# control.net
KiCad netlist of a schematic drawn in EAGLE
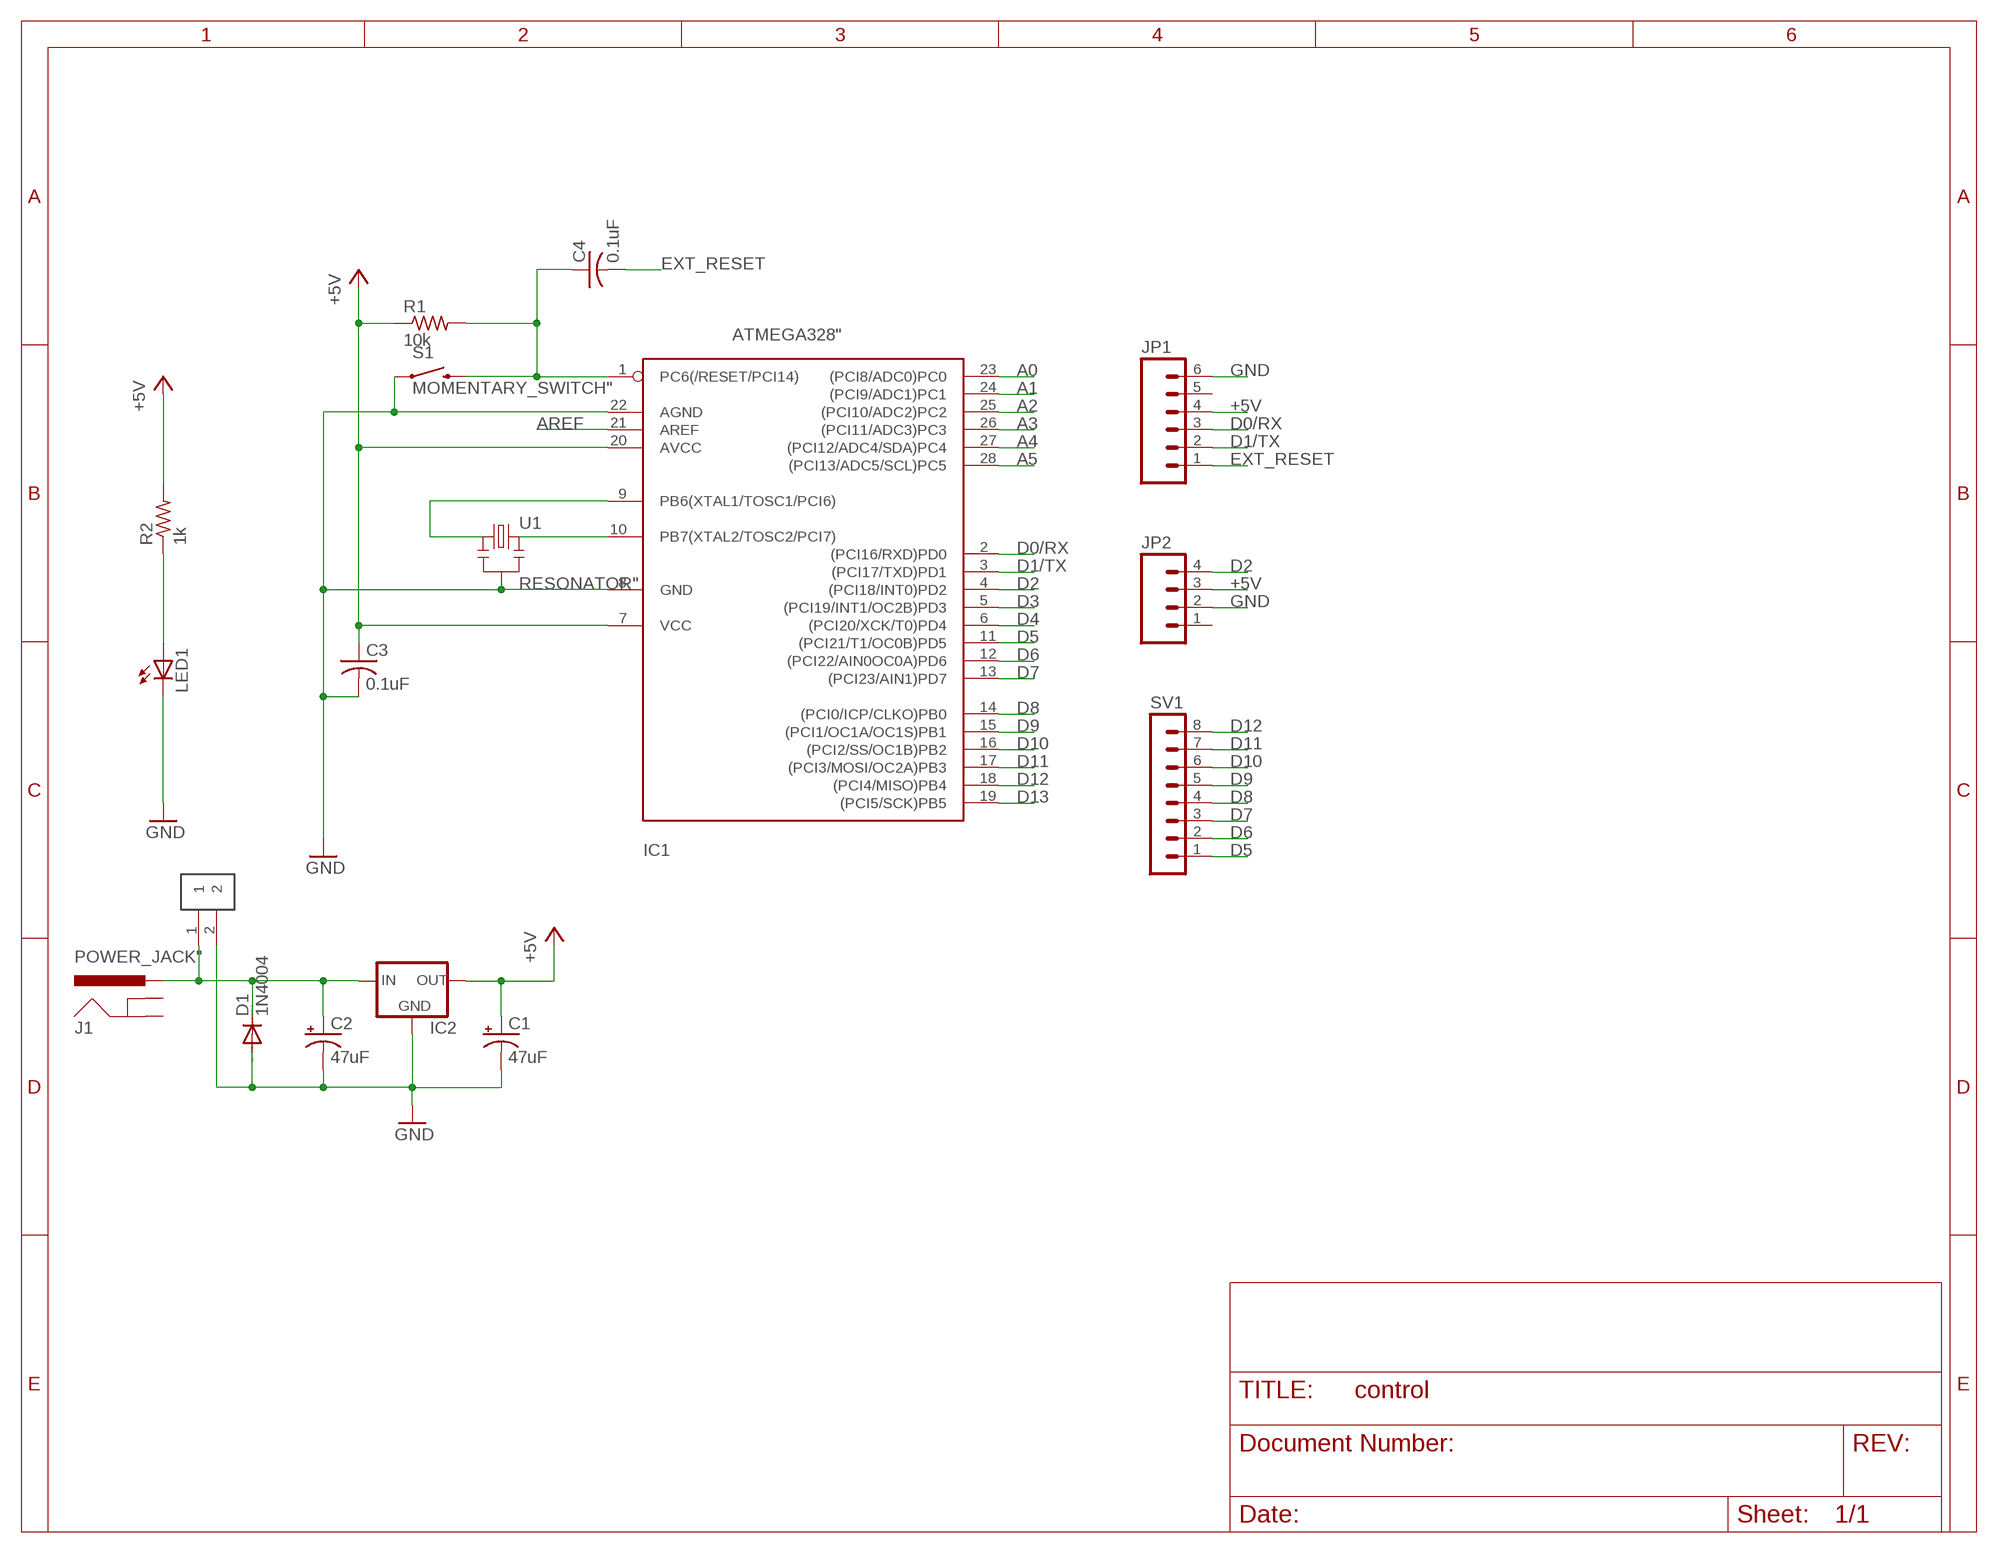
[diagram p0: schematic, sheet 1]

(export (version "E")
  (design (tool "Eeschema 10.0.6"))
  (components
    (comp (ref "C1")
      (value "47uF")
      (footprint "eagle-import:ELECTROLYTIC_CAP")
      (libsource (lib "eagle-import") (part "ELECTROLYTIC_CAP2.54MM"))
    )
    (comp (ref "C2")
      (value "47uF")
      (footprint "eagle-import:ELECTROLYTIC_CAP")
      (libsource (lib "eagle-import") (part "ELECTROLYTIC_CAP2.54MM"))
    )
    (comp (ref "C3")
      (value "0.1uF")
      (footprint "eagle-import:UNPOLARIZED_CAP")
      (libsource (lib "eagle-import") (part "UNPOLARIZED_CAP{dblquote}"))
    )
    (comp (ref "C4")
      (value "0.1uF")
      (footprint "eagle-import:UNPOLARIZED_CAP")
      (libsource (lib "eagle-import") (part "UNPOLARIZED_CAP{dblquote}"))
    )
    (comp (ref "D1")
      (value "1N4004")
      (footprint "eagle-import:DO41-10")
      (libsource (lib "eagle-import") (part "1N4004"))
    )
    (comp (ref "IC1")
      (value "ATMEGA328\"")
      (footprint "eagle-import:ATMEGA328")
      (libsource (lib "eagle-import") (part "ATMEGA328{dblquote}"))
    )
    (comp (ref "IC2")
      (value "REGULATOR")
      (footprint "eagle-import:L4931_REGULATOR")
      (libsource (lib "eagle-import") (part "REGULATOR"))
    )
    (comp (ref "J1")
      (value "POWER_JACK\"")
      (footprint "eagle-import:POWER_JACK")
      (libsource (lib "eagle-import") (part "POWER_JACK{dblquote}"))
    )
    (comp (ref "JP1")
      (value "1X06_HEADER\"")
      (footprint "eagle-import:1X06_HEADER")
      (libsource (lib "eagle-import") (part "1X06_HEADER{dblquote}"))
    )
    (comp (ref "JP2")
      (value "1X04_HEADER\"")
      (footprint "eagle-import:1X04_HEADER")
      (libsource (lib "eagle-import") (part "1X04_HEADER{dblquote}"))
    )
    (comp (ref "LED1")
      (value "LED3MM")
      (footprint "eagle-import:LED")
      (libsource (lib "eagle-import") (part "LED3MM"))
    )
    (comp (ref "R1")
      (value "10k")
      (footprint "eagle-import:RESISTOR")
      (libsource (lib "eagle-import") (part "RESISTOR1/6WATT"))
    )
    (comp (ref "R2")
      (value "1k")
      (footprint "eagle-import:RESISTOR")
      (libsource (lib "eagle-import") (part "RESISTOR1/6WATT"))
    )
    (comp (ref "S1")
      (value "MOMENTARY_SWITCH\"")
      (footprint "eagle-import:MOMENTARY_SWITCH")
      (libsource (lib "eagle-import") (part "MOMENTARY_SWITCH{dblquote}"))
    )
    (comp (ref "SV1")
      (value "MA08-1")
      (footprint "eagle-import:MA08-1")
      (libsource (lib "eagle-import") (part "MA08-1"))
    )
    (comp (ref "U$1")
      (value "1X02_HEADER")
      (footprint "eagle-import:1X02_HEADER")
      (libsource (lib "eagle-import") (part "1X02_HEADER"))
    )
    (comp (ref "U1")
      (value "RESONATOR\"")
      (footprint "eagle-import:RESONATOR")
      (libsource (lib "eagle-import") (part "RESONATOR{dblquote}"))
    )
  )
  (nets
    (net (code "1") (name "+5V") (class "Default")
      (node (ref "C1") (pin "+") (pinfunction "+_+") (pintype "passive"))
      (node (ref "C3") (pin "1") (pinfunction "1_1") (pintype "passive"))
      (node (ref "IC1") (pin "20") (pinfunction "AVCC_20") (pintype "bidirectional"))
      (node (ref "IC1") (pin "7") (pinfunction "VCC_7") (pintype "bidirectional"))
      (node (ref "IC2") (pin "OUT") (pinfunction "OUT_OUT") (pintype "passive"))
      (node (ref "JP1") (pin "4") (pinfunction "4_4") (pintype "passive"))
      (node (ref "JP2") (pin "3") (pinfunction "3_3") (pintype "passive"))
      (node (ref "R1") (pin "1") (pinfunction "1_1") (pintype "passive"))
      (node (ref "R2") (pin "2") (pinfunction "2_2") (pintype "passive"))
    )
    (net (code "2") (name "/A0") (class "Default")
      (node (ref "IC1") (pin "23") (pinfunction "(PCI8/ADC0)PC0_23") (pintype "bidirectional"))
    )
    (net (code "3") (name "/A1") (class "Default")
      (node (ref "IC1") (pin "24") (pinfunction "(PCI9/ADC1)PC1_24") (pintype "bidirectional"))
    )
    (net (code "4") (name "/A2") (class "Default")
      (node (ref "IC1") (pin "25") (pinfunction "(PCI10/ADC2)PC2_25") (pintype "bidirectional"))
    )
    (net (code "5") (name "/A3") (class "Default")
      (node (ref "IC1") (pin "26") (pinfunction "(PCI11/ADC3)PC3_26") (pintype "bidirectional"))
    )
    (net (code "6") (name "/A4") (class "Default")
      (node (ref "IC1") (pin "27") (pinfunction "(PCI12/ADC4/SDA)PC4_27") (pintype "bidirectional"))
    )
    (net (code "7") (name "/A5") (class "Default")
      (node (ref "IC1") (pin "28") (pinfunction "(PCI13/ADC5/SCL)PC5_28") (pintype "bidirectional"))
    )
    (net (code "8") (name "/AREF") (class "Default")
      (node (ref "IC1") (pin "21") (pinfunction "AREF_21") (pintype "bidirectional"))
    )
    (net (code "9") (name "/D0{slash}RX") (class "Default")
      (node (ref "IC1") (pin "2") (pinfunction "(PCI16/RXD)PD0_2") (pintype "bidirectional"))
      (node (ref "JP1") (pin "3") (pinfunction "3_3") (pintype "passive"))
    )
    (net (code "10") (name "/D1{slash}TX") (class "Default")
      (node (ref "IC1") (pin "3") (pinfunction "(PCI17/TXD)PD1_3") (pintype "bidirectional"))
      (node (ref "JP1") (pin "2") (pinfunction "2_2") (pintype "passive"))
    )
    (net (code "11") (name "/D2") (class "Default")
      (node (ref "IC1") (pin "4") (pinfunction "(PCI18/INT0)PD2_4") (pintype "bidirectional"))
      (node (ref "JP2") (pin "4") (pinfunction "4_4") (pintype "passive"))
    )
    (net (code "12") (name "/D3") (class "Default")
      (node (ref "IC1") (pin "5") (pinfunction "(PCI19/INT1/OC2B)PD3_5") (pintype "bidirectional"))
    )
    (net (code "13") (name "/D4") (class "Default")
      (node (ref "IC1") (pin "6") (pinfunction "(PCI20/XCK/T0)PD4_6") (pintype "bidirectional"))
    )
    (net (code "14") (name "/D5") (class "Default")
      (node (ref "IC1") (pin "11") (pinfunction "(PCI21/T1/OC0B)PD5_11") (pintype "bidirectional"))
      (node (ref "SV1") (pin "1") (pinfunction "1_1") (pintype "passive"))
    )
    (net (code "15") (name "/D6") (class "Default")
      (node (ref "IC1") (pin "12") (pinfunction "(PCI22/AIN0OC0A)PD6_12") (pintype "bidirectional"))
      (node (ref "SV1") (pin "2") (pinfunction "2_2") (pintype "passive"))
    )
    (net (code "16") (name "/D7") (class "Default")
      (node (ref "IC1") (pin "13") (pinfunction "(PCI23/AIN1)PD7_13") (pintype "bidirectional"))
      (node (ref "SV1") (pin "3") (pinfunction "3_3") (pintype "passive"))
    )
    (net (code "17") (name "/D8") (class "Default")
      (node (ref "IC1") (pin "14") (pinfunction "(PCI0/ICP/CLKO)PB0_14") (pintype "bidirectional"))
      (node (ref "SV1") (pin "4") (pinfunction "4_4") (pintype "passive"))
    )
    (net (code "18") (name "/D9") (class "Default")
      (node (ref "IC1") (pin "15") (pinfunction "(PCI1/OC1A/OC1S)PB1_15") (pintype "bidirectional"))
      (node (ref "SV1") (pin "5") (pinfunction "5_5") (pintype "passive"))
    )
    (net (code "19") (name "/D10") (class "Default")
      (node (ref "IC1") (pin "16") (pinfunction "(PCI2/SS/OC1B)PB2_16") (pintype "bidirectional"))
      (node (ref "SV1") (pin "6") (pinfunction "6_6") (pintype "passive"))
    )
    (net (code "20") (name "/D11") (class "Default")
      (node (ref "IC1") (pin "17") (pinfunction "(PCI3/MOSI/OC2A)PB3_17") (pintype "bidirectional"))
      (node (ref "SV1") (pin "7") (pinfunction "7_7") (pintype "passive"))
    )
    (net (code "21") (name "/D12") (class "Default")
      (node (ref "IC1") (pin "18") (pinfunction "(PCI4/MISO)PB4_18") (pintype "bidirectional"))
      (node (ref "SV1") (pin "8") (pinfunction "8_8") (pintype "passive"))
    )
    (net (code "22") (name "/D13") (class "Default")
      (node (ref "IC1") (pin "19") (pinfunction "(PCI5/SCK)PB5_19") (pintype "bidirectional"))
    )
    (net (code "23") (name "/EXT_RESET") (class "Default")
      (node (ref "C4") (pin "2") (pinfunction "2_2") (pintype "passive"))
      (node (ref "JP1") (pin "1") (pinfunction "1_1") (pintype "passive"))
    )
    (net (code "24") (name "GND") (class "Default")
      (node (ref "C1") (pin "-") (pinfunction "-_-") (pintype "passive"))
      (node (ref "C2") (pin "-") (pinfunction "-_-") (pintype "passive"))
      (node (ref "C3") (pin "2") (pinfunction "2_2") (pintype "passive"))
      (node (ref "D1") (pin "A") (pinfunction "A_A") (pintype "passive"))
      (node (ref "IC1") (pin "22") (pinfunction "AGND_22") (pintype "bidirectional"))
      (node (ref "IC1") (pin "8") (pinfunction "GND_8") (pintype "bidirectional"))
      (node (ref "IC2") (pin "GND") (pinfunction "GND_GND") (pintype "input"))
      (node (ref "JP1") (pin "6") (pinfunction "6_6") (pintype "passive"))
      (node (ref "JP2") (pin "2") (pinfunction "2_2") (pintype "passive"))
      (node (ref "LED1") (pin "K") (pinfunction "C_K") (pintype "passive"))
      (node (ref "S1") (pin "1") (pinfunction "1_1") (pintype "passive"))
      (node (ref "U$1") (pin "2") (pinfunction "2_2") (pintype "bidirectional"))
      (node (ref "U1") (pin "2") (pinfunction "2_2") (pintype "passive"))
    )
    (net (code "25") (name "Net-(C2-Pad+)") (class "Default")
      (node (ref "C2") (pin "+") (pinfunction "+_+") (pintype "passive"))
      (node (ref "D1") (pin "C") (pinfunction "C_C") (pintype "passive"))
      (node (ref "IC2") (pin "IN") (pinfunction "IN_IN") (pintype "input"))
      (node (ref "J1") (pin "PWR") (pinfunction "PWR_PWR") (pintype "bidirectional"))
      (node (ref "U$1") (pin "1") (pinfunction "1_1") (pintype "bidirectional"))
    )
    (net (code "26") (name "Net-(IC1-PB6(XTAL1{slash}TOSC1{slash}PCI6))") (class "Default")
      (node (ref "IC1") (pin "9") (pinfunction "PB6(XTAL1/TOSC1/PCI6)_9") (pintype "bidirectional"))
      (node (ref "U1") (pin "1") (pinfunction "1_1") (pintype "passive"))
    )
    (net (code "27") (name "Net-(IC1-PB7(XTAL2{slash}TOSC2{slash}PCI7))") (class "Default")
      (node (ref "IC1") (pin "10") (pinfunction "PB7(XTAL2/TOSC2/PCI7)_10") (pintype "bidirectional"))
      (node (ref "U1") (pin "3") (pinfunction "3_3") (pintype "passive"))
    )
    (net (code "28") (name "Net-(IC1-PC6({slash}RESET{slash}PCI14))") (class "Default")
      (node (ref "C4") (pin "1") (pinfunction "1_1") (pintype "passive"))
      (node (ref "IC1") (pin "1") (pinfunction "PC6(/RESET/PCI14)_1") (pintype "bidirectional"))
      (node (ref "R1") (pin "2") (pinfunction "2_2") (pintype "passive"))
      (node (ref "S1") (pin "3") (pinfunction "2_3") (pintype "passive"))
    )
    (net (code "29") (name "Net-(LED1-PadA)") (class "Default")
      (node (ref "LED1") (pin "A") (pinfunction "A_A") (pintype "passive"))
      (node (ref "R2") (pin "1") (pinfunction "1_1") (pintype "passive"))
    )
    (net (code "30") (name "unconnected-(J1-PadGND)") (class "Default")
      (node (ref "J1") (pin "GND") (pinfunction "GND_GND") (pintype "bidirectional"))
    )
    (net (code "31") (name "unconnected-(J1-PadGNDBREAK)") (class "Default")
      (node (ref "J1") (pin "GNDBREAK") (pinfunction "GNDBREAK_GNDBREAK") (pintype "bidirectional"))
    )
    (net (code "32") (name "unconnected-(JP1-Pad5)") (class "Default")
      (node (ref "JP1") (pin "5") (pinfunction "5_5") (pintype "passive"))
    )
    (net (code "33") (name "unconnected-(JP2-Pad1)") (class "Default")
      (node (ref "JP2") (pin "1") (pinfunction "1_1") (pintype "passive"))
    )
  )
)
